# SCH_SIM.net
KiCad netlist of a schematic drawn in Altium Designer
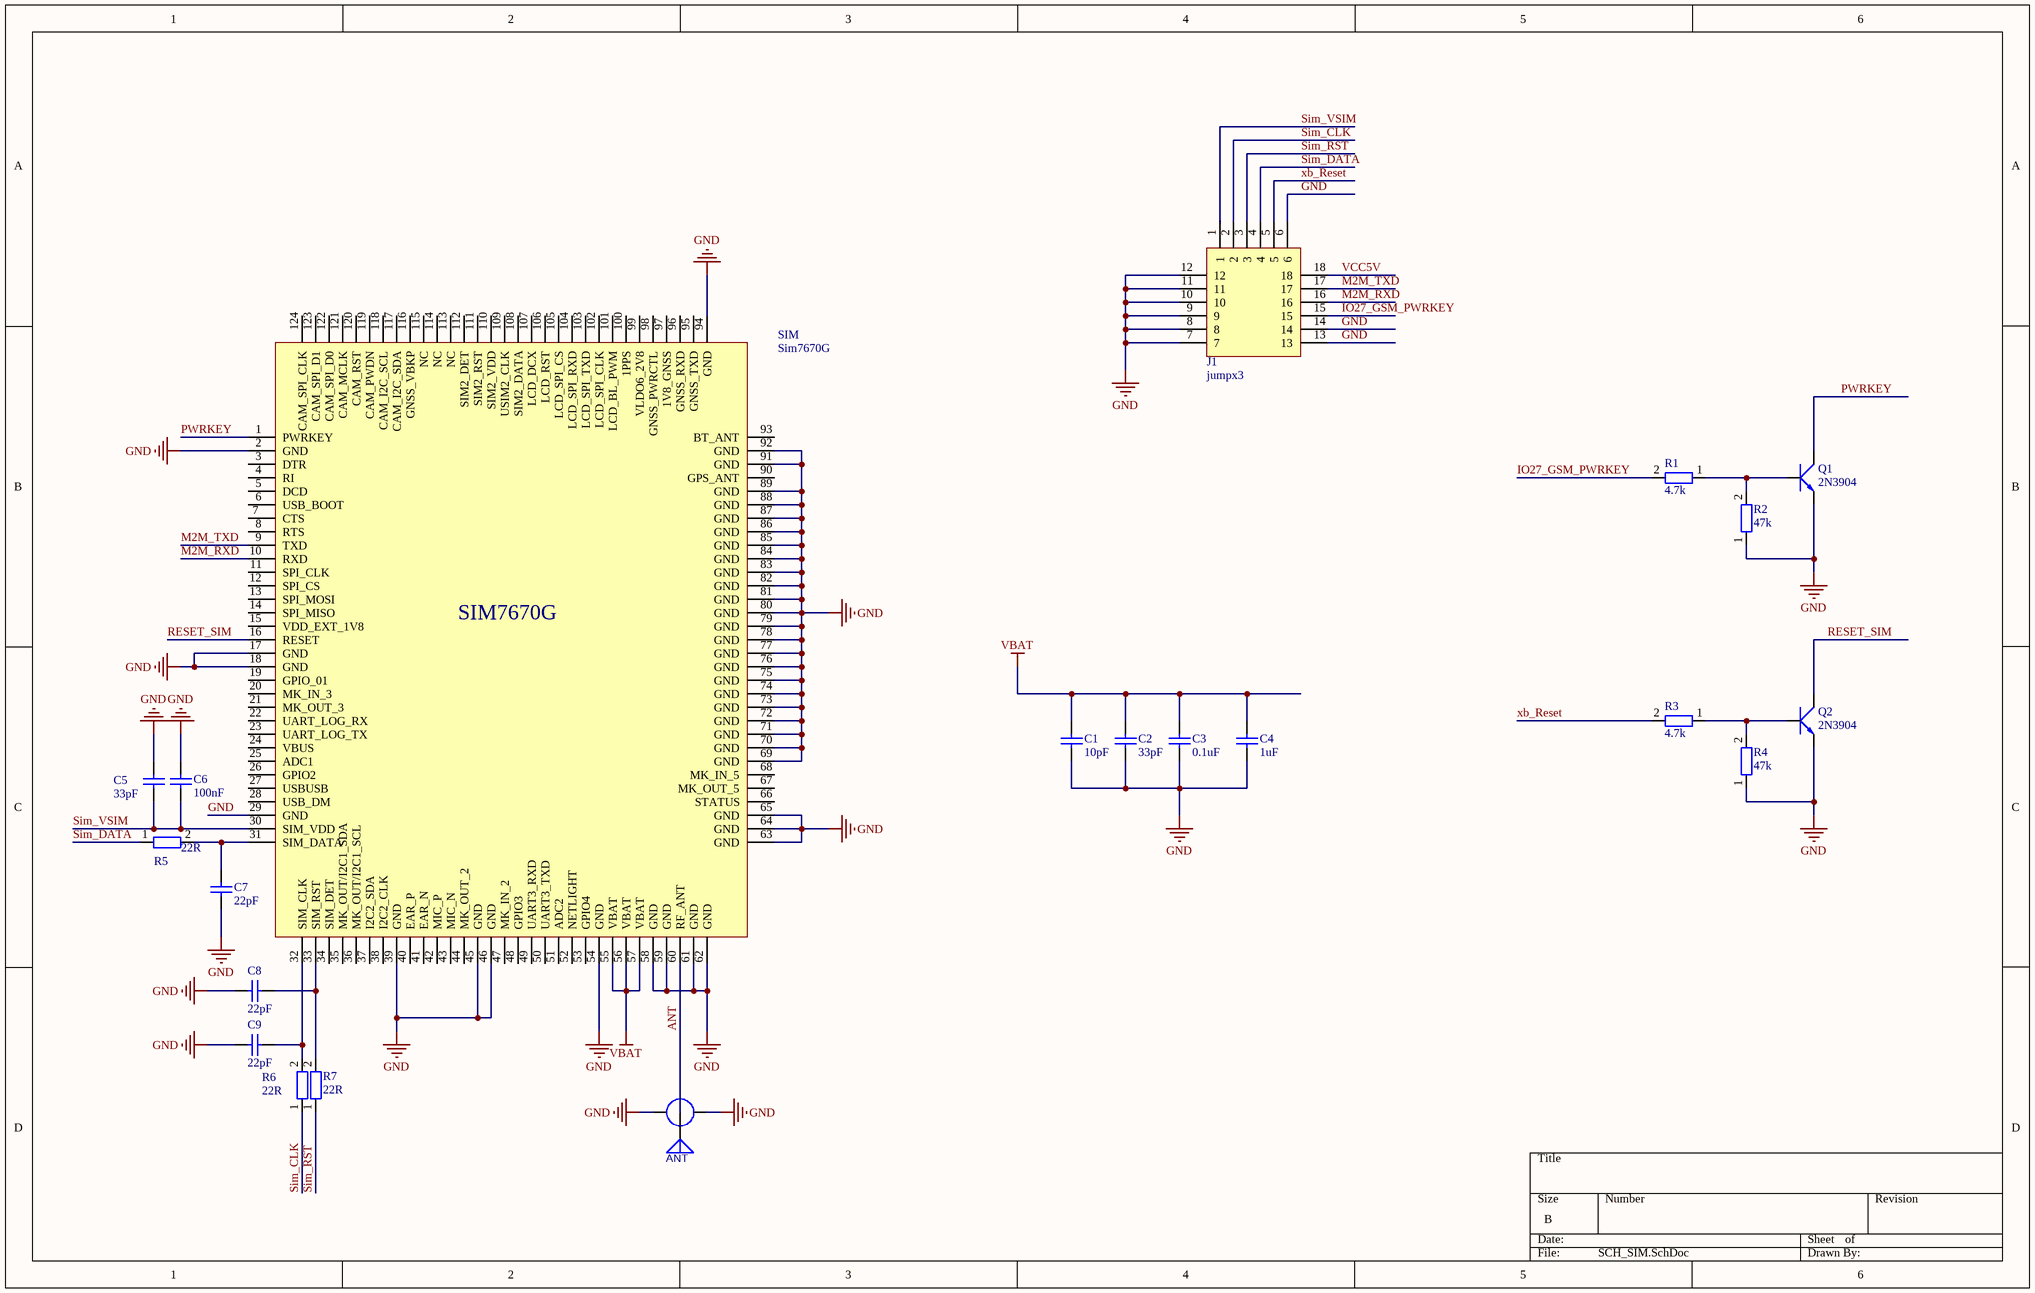
[diagram p0: SCH_SIM.SchDoc]

(export (version "E")
  (design (tool "Eeschema 10.0.6"))
  (components
    (comp (ref "ANT")
      (value "ANT")
      (footprint "CONNECTORS RF SMD TYPE IPEX")
      (description "SMD RF Connectors / Coaxial Connectors ROHS")
      (fields
        (field (name "BOM_SUPPLIER PART") "C3151745")
        (field (name "BOM_MANUFACTURER PART") "IPEX1-TXZ 142")
        (field (name "CONTRIBUTOR") "lcsc")
      )
      (libsource (lib "SCH_Library") (part "CONNECTORS RF SMD"))
    )
    (comp (ref "C1")
      (value "10pF")
      (footprint "CAP_0805")
      (description "Capacitor")
      (libsource (lib "SCH_Library") (part "CAP104-100nF-50V"))
    )
    (comp (ref "C2")
      (value "33pF")
      (footprint "CAP_0805")
      (description "Capacitor")
      (libsource (lib "SCH_Library") (part "CAP104-100nF-50V"))
    )
    (comp (ref "C3")
      (value "0.1uF")
      (footprint "CAP_0805")
      (description "Capacitor")
      (libsource (lib "SCH_Library") (part "CAP104-100nF-50V"))
    )
    (comp (ref "C4")
      (value "1uF")
      (footprint "CAP_0805")
      (description "Capacitor")
      (libsource (lib "SCH_Library") (part "CAP104-100nF-50V"))
    )
    (comp (ref "C5")
      (value "33pF")
      (footprint "CAP_0805")
      (description "Capacitor")
      (libsource (lib "SCH_Library") (part "CAP104-100nF-50V"))
    )
    (comp (ref "C6")
      (value "100nF")
      (footprint "CAP_0805")
      (description "Capacitor")
      (libsource (lib "SCH_Library") (part "CAP104-100nF-50V"))
    )
    (comp (ref "C7")
      (value "22pF")
      (footprint "CAP_0805")
      (description "Capacitor")
      (libsource (lib "SCH_Library") (part "CAP104-100nF-50V"))
    )
    (comp (ref "C8")
      (value "22pF")
      (footprint "CAP_0805")
      (description "Capacitor")
      (libsource (lib "SCH_Library") (part "CAP104-100nF-50V"))
    )
    (comp (ref "C9")
      (value "22pF")
      (footprint "CAP_0805")
      (description "Capacitor")
      (libsource (lib "SCH_Library") (part "CAP104-100nF-50V"))
    )
    (comp (ref "J1") (value "jumpx3") (libsource (lib "SCH_Library") (part "jumpx3")))
    (comp (ref "Q1")
      (value "2N3904")
      (footprint "SOT-23")
      (description "SOT-23 - C8658")
      (libsource (lib "Altium_Lib") (part "Trans BC817"))
    )
    (comp (ref "Q2")
      (value "2N3904")
      (footprint "SOT-23")
      (description "SOT-23 - C8658")
      (libsource (lib "Altium_Lib") (part "Trans BC817"))
    )
    (comp (ref "R1")
      (value "4.7k")
      (footprint "RES CHIPS SMD 0603 TYPE 1608")
      (description "±1% - Chip Resistor - Surface Mount ROHS")
      (libsource (lib "SCH_Library") (part "RES 0603 1%_"))
    )
    (comp (ref "R2")
      (value "47k")
      (footprint "RES CHIPS SMD 0603 TYPE 1608")
      (description "±1% - Chip Resistor - Surface Mount ROHS")
      (libsource (lib "SCH_Library") (part "RES 0603 1%_"))
    )
    (comp (ref "R3")
      (value "4.7k")
      (footprint "RES CHIPS SMD 0603 TYPE 1608")
      (description "±1% - Chip Resistor - Surface Mount ROHS")
      (libsource (lib "SCH_Library") (part "RES 0603 1%_"))
    )
    (comp (ref "R4")
      (value "47k")
      (footprint "RES CHIPS SMD 0603 TYPE 1608")
      (description "±1% - Chip Resistor - Surface Mount ROHS")
      (libsource (lib "SCH_Library") (part "RES 0603 1%_"))
    )
    (comp (ref "R5")
      (value "22R")
      (footprint "RES CHIPS SMD 0603 TYPE 1608")
      (description "±1% - Chip Resistor - Surface Mount ROHS")
      (libsource (lib "SCH_Library") (part "RES 0603 1%_"))
    )
    (comp (ref "R6")
      (value "22R")
      (footprint "RES CHIPS SMD 0603 TYPE 1608")
      (description "±1% - Chip Resistor - Surface Mount ROHS")
      (libsource (lib "SCH_Library") (part "RES 0603 1%_"))
    )
    (comp (ref "R7")
      (value "22R")
      (footprint "RES CHIPS SMD 0603 TYPE 1608")
      (description "±1% - Chip Resistor - Surface Mount ROHS")
      (libsource (lib "SCH_Library") (part "RES 0603 1%_"))
    )
    (comp (ref "SIM")
      (value "Sim7670G")
      (footprint "SIM7670")
      (libsource (lib "SCH_Library") (part "Sim7670G"))
    )
  )
  (nets
    (net (code "1") (name "/ANT") (class "Default")
      (node (ref "ANT") (pin "1") (pinfunction "1_1") (pintype "passive"))
      (node (ref "SIM") (pin "60") (pinfunction "RF_ANT_60") (pintype "passive"))
    )
    (net (code "2") (name "/IO27_GSM_PWRKEY") (class "Default")
      (node (ref "J1") (pin "15") (pinfunction "15_15") (pintype "passive"))
      (node (ref "R1") (pin "2") (pinfunction "2_2") (pintype "passive"))
    )
    (net (code "3") (name "/M2M_RXD") (class "Default")
      (node (ref "J1") (pin "16") (pinfunction "16_16") (pintype "passive"))
      (node (ref "SIM") (pin "10") (pinfunction "RXD_10") (pintype "passive"))
    )
    (net (code "4") (name "/M2M_TXD") (class "Default")
      (node (ref "J1") (pin "17") (pinfunction "17_17") (pintype "passive"))
      (node (ref "SIM") (pin "9") (pinfunction "TXD_9") (pintype "passive"))
    )
    (net (code "5") (name "/PWRKEY") (class "Default")
      (node (ref "Q1") (pin "3") (pinfunction "C_3") (pintype "passive"))
      (node (ref "SIM") (pin "1") (pinfunction "PWRKEY_1") (pintype "passive"))
    )
    (net (code "6") (name "/RESET_SIM") (class "Default")
      (node (ref "Q2") (pin "3") (pinfunction "C_3") (pintype "passive"))
      (node (ref "SIM") (pin "16") (pinfunction "RESET_16") (pintype "passive"))
    )
    (net (code "7") (name "/Sim_CLK") (class "Default")
      (node (ref "J1") (pin "2") (pinfunction "2_2") (pintype "passive"))
      (node (ref "R6") (pin "1") (pinfunction "1_1") (pintype "passive"))
    )
    (net (code "8") (name "/Sim_DATA") (class "Default")
      (node (ref "J1") (pin "4") (pinfunction "4_4") (pintype "passive"))
      (node (ref "R5") (pin "1") (pinfunction "1_1") (pintype "passive"))
    )
    (net (code "9") (name "/Sim_RST") (class "Default")
      (node (ref "J1") (pin "3") (pinfunction "3_3") (pintype "passive"))
      (node (ref "R7") (pin "1") (pinfunction "1_1") (pintype "passive"))
    )
    (net (code "10") (name "/Sim_VSIM") (class "Default")
      (node (ref "C5") (pin "2") (pinfunction "2_2") (pintype "passive"))
      (node (ref "C6") (pin "2") (pinfunction "2_2") (pintype "passive"))
      (node (ref "J1") (pin "1") (pinfunction "1_1") (pintype "passive"))
      (node (ref "SIM") (pin "30") (pinfunction "SIM_VDD_30") (pintype "passive"))
    )
    (net (code "11") (name "/VCC5V") (class "Default")
      (node (ref "J1") (pin "18") (pinfunction "18_18") (pintype "passive"))
    )
    (net (code "12") (name "/xb_Reset") (class "Default")
      (node (ref "J1") (pin "5") (pinfunction "5_5") (pintype "passive"))
      (node (ref "R3") (pin "2") (pinfunction "2_2") (pintype "passive"))
    )
    (net (code "13") (name "GND") (class "Default")
      (node (ref "ANT") (pin "2") (pinfunction "2_2") (pintype "passive"))
      (node (ref "ANT") (pin "3") (pinfunction "3_3") (pintype "passive"))
      (node (ref "C1") (pin "1") (pinfunction "1_1") (pintype "passive"))
      (node (ref "C2") (pin "1") (pinfunction "1_1") (pintype "passive"))
      (node (ref "C3") (pin "1") (pinfunction "1_1") (pintype "passive"))
      (node (ref "C4") (pin "1") (pinfunction "1_1") (pintype "passive"))
      (node (ref "C5") (pin "1") (pinfunction "1_1") (pintype "passive"))
      (node (ref "C6") (pin "1") (pinfunction "1_1") (pintype "passive"))
      (node (ref "C7") (pin "2") (pinfunction "2_2") (pintype "passive"))
      (node (ref "C8") (pin "2") (pinfunction "2_2") (pintype "passive"))
      (node (ref "C9") (pin "2") (pinfunction "2_2") (pintype "passive"))
      (node (ref "J1") (pin "10") (pinfunction "10_10") (pintype "passive"))
      (node (ref "J1") (pin "11") (pinfunction "11_11") (pintype "passive"))
      (node (ref "J1") (pin "12") (pinfunction "12_12") (pintype "passive"))
      (node (ref "J1") (pin "13") (pinfunction "13_13") (pintype "passive"))
      (node (ref "J1") (pin "14") (pinfunction "14_14") (pintype "passive"))
      (node (ref "J1") (pin "6") (pinfunction "6_6") (pintype "passive"))
      (node (ref "J1") (pin "7") (pinfunction "7_7") (pintype "passive"))
      (node (ref "J1") (pin "8") (pinfunction "8_8") (pintype "passive"))
      (node (ref "J1") (pin "9") (pinfunction "9_9") (pintype "passive"))
      (node (ref "Q1") (pin "2") (pinfunction "E_2") (pintype "passive"))
      (node (ref "Q2") (pin "2") (pinfunction "E_2") (pintype "passive"))
      (node (ref "R2") (pin "1") (pinfunction "1_1") (pintype "passive"))
      (node (ref "R4") (pin "1") (pinfunction "1_1") (pintype "passive"))
      (node (ref "SIM") (pin "17") (pinfunction "GND_17") (pintype "passive"))
      (node (ref "SIM") (pin "18") (pinfunction "GND_18") (pintype "passive"))
      (node (ref "SIM") (pin "2") (pinfunction "GND_2") (pintype "passive"))
      (node (ref "SIM") (pin "29") (pinfunction "GND_29") (pintype "passive"))
      (node (ref "SIM") (pin "39") (pinfunction "GND_39") (pintype "passive"))
      (node (ref "SIM") (pin "45") (pinfunction "GND_45") (pintype "passive"))
      (node (ref "SIM") (pin "46") (pinfunction "GND_46") (pintype "passive"))
      (node (ref "SIM") (pin "54") (pinfunction "GND_54") (pintype "passive"))
      (node (ref "SIM") (pin "58") (pinfunction "GND_58") (pintype "passive"))
      (node (ref "SIM") (pin "59") (pinfunction "GND_59") (pintype "passive"))
      (node (ref "SIM") (pin "61") (pinfunction "GND_61") (pintype "passive"))
      (node (ref "SIM") (pin "62") (pinfunction "GND_62") (pintype "passive"))
      (node (ref "SIM") (pin "63") (pinfunction "GND_63") (pintype "passive"))
      (node (ref "SIM") (pin "64") (pinfunction "GND_64") (pintype "passive"))
      (node (ref "SIM") (pin "65") (pinfunction "GND_65") (pintype "passive"))
      (node (ref "SIM") (pin "69") (pinfunction "GND_69") (pintype "passive"))
      (node (ref "SIM") (pin "70") (pinfunction "GND_70") (pintype "passive"))
      (node (ref "SIM") (pin "71") (pinfunction "GND_71") (pintype "passive"))
      (node (ref "SIM") (pin "72") (pinfunction "GND_72") (pintype "passive"))
      (node (ref "SIM") (pin "73") (pinfunction "GND_73") (pintype "passive"))
      (node (ref "SIM") (pin "74") (pinfunction "GND_74") (pintype "passive"))
      (node (ref "SIM") (pin "75") (pinfunction "GND_75") (pintype "passive"))
      (node (ref "SIM") (pin "76") (pinfunction "GND_76") (pintype "passive"))
      (node (ref "SIM") (pin "77") (pinfunction "GND_77") (pintype "passive"))
      (node (ref "SIM") (pin "78") (pinfunction "GND_78") (pintype "passive"))
      (node (ref "SIM") (pin "79") (pinfunction "GND_79") (pintype "passive"))
      (node (ref "SIM") (pin "80") (pinfunction "GND_80") (pintype "passive"))
      (node (ref "SIM") (pin "81") (pinfunction "GND_81") (pintype "passive"))
      (node (ref "SIM") (pin "82") (pinfunction "GND_82") (pintype "passive"))
      (node (ref "SIM") (pin "83") (pinfunction "GND_83") (pintype "passive"))
      (node (ref "SIM") (pin "84") (pinfunction "GND_84") (pintype "passive"))
      (node (ref "SIM") (pin "85") (pinfunction "GND_85") (pintype "passive"))
      (node (ref "SIM") (pin "86") (pinfunction "GND_86") (pintype "passive"))
      (node (ref "SIM") (pin "87") (pinfunction "GND_87") (pintype "passive"))
      (node (ref "SIM") (pin "88") (pinfunction "GND_88") (pintype "passive"))
      (node (ref "SIM") (pin "89") (pinfunction "GND_89") (pintype "passive"))
      (node (ref "SIM") (pin "91") (pinfunction "GND_91") (pintype "passive"))
      (node (ref "SIM") (pin "92") (pinfunction "GND_92") (pintype "passive"))
      (node (ref "SIM") (pin "94") (pinfunction "GND_94") (pintype "passive"))
    )
    (net (code "14") (name "Net-(Q1-B)") (class "Default")
      (node (ref "Q1") (pin "1") (pinfunction "B_1") (pintype "passive"))
      (node (ref "R1") (pin "1") (pinfunction "1_1") (pintype "passive"))
      (node (ref "R2") (pin "2") (pinfunction "2_2") (pintype "passive"))
    )
    (net (code "15") (name "Net-(Q2-B)") (class "Default")
      (node (ref "Q2") (pin "1") (pinfunction "B_1") (pintype "passive"))
      (node (ref "R3") (pin "1") (pinfunction "1_1") (pintype "passive"))
      (node (ref "R4") (pin "2") (pinfunction "2_2") (pintype "passive"))
    )
    (net (code "16") (name "Net-(SIM-SIM_CLK)") (class "Default")
      (node (ref "C9") (pin "1") (pinfunction "1_1") (pintype "passive"))
      (node (ref "R6") (pin "2") (pinfunction "2_2") (pintype "passive"))
      (node (ref "SIM") (pin "32") (pinfunction "SIM_CLK_32") (pintype "passive"))
    )
    (net (code "17") (name "Net-(SIM-SIM_DATA)") (class "Default")
      (node (ref "C7") (pin "1") (pinfunction "1_1") (pintype "passive"))
      (node (ref "R5") (pin "2") (pinfunction "2_2") (pintype "passive"))
      (node (ref "SIM") (pin "31") (pinfunction "SIM_DATA_31") (pintype "passive"))
    )
    (net (code "18") (name "Net-(SIM-SIM_RST)") (class "Default")
      (node (ref "C8") (pin "1") (pinfunction "1_1") (pintype "passive"))
      (node (ref "R7") (pin "2") (pinfunction "2_2") (pintype "passive"))
      (node (ref "SIM") (pin "33") (pinfunction "SIM_RST_33") (pintype "passive"))
    )
    (net (code "19") (name "VBAT") (class "Default")
      (node (ref "C1") (pin "2") (pinfunction "2_2") (pintype "passive"))
      (node (ref "C2") (pin "2") (pinfunction "2_2") (pintype "passive"))
      (node (ref "C3") (pin "2") (pinfunction "2_2") (pintype "passive"))
      (node (ref "C4") (pin "2") (pinfunction "2_2") (pintype "passive"))
      (node (ref "SIM") (pin "55") (pinfunction "VBAT_55") (pintype "passive"))
      (node (ref "SIM") (pin "56") (pinfunction "VBAT_56") (pintype "passive"))
      (node (ref "SIM") (pin "57") (pinfunction "VBAT_57") (pintype "passive"))
    )
    (net (code "20") (name "unconnected-(SIM-1PPS-Pad100)") (class "Default")
      (node (ref "SIM") (pin "100") (pinfunction "1PPS_100") (pintype "passive"))
    )
    (net (code "21") (name "unconnected-(SIM-1V8_GNSS-Pad97)") (class "Default")
      (node (ref "SIM") (pin "97") (pinfunction "1V8_GNSS_97") (pintype "passive"))
    )
    (net (code "22") (name "unconnected-(SIM-ADC1-Pad25)") (class "Default")
      (node (ref "SIM") (pin "25") (pinfunction "ADC1_25") (pintype "passive"))
    )
    (net (code "23") (name "unconnected-(SIM-ADC2-Pad51)") (class "Default")
      (node (ref "SIM") (pin "51") (pinfunction "ADC2_51") (pintype "passive"))
    )
    (net (code "24") (name "unconnected-(SIM-BT_ANT-Pad93)") (class "Default")
      (node (ref "SIM") (pin "93") (pinfunction "BT_ANT_93") (pintype "passive"))
    )
    (net (code "25") (name "unconnected-(SIM-CAM_I2C_SCL-Pad118)") (class "Default")
      (node (ref "SIM") (pin "118") (pinfunction "CAM_I2C_SCL_118") (pintype "passive"))
    )
    (net (code "26") (name "unconnected-(SIM-CAM_I2C_SDA-Pad117)") (class "Default")
      (node (ref "SIM") (pin "117") (pinfunction "CAM_I2C_SDA_117") (pintype "passive"))
    )
    (net (code "27") (name "unconnected-(SIM-CAM_MCLK-Pad121)") (class "Default")
      (node (ref "SIM") (pin "121") (pinfunction "CAM_MCLK_121") (pintype "passive"))
    )
    (net (code "28") (name "unconnected-(SIM-CAM_PWDN-Pad119)") (class "Default")
      (node (ref "SIM") (pin "119") (pinfunction "CAM_PWDN_119") (pintype "passive"))
    )
    (net (code "29") (name "unconnected-(SIM-CAM_RST-Pad120)") (class "Default")
      (node (ref "SIM") (pin "120") (pinfunction "CAM_RST_120") (pintype "passive"))
    )
    (net (code "30") (name "unconnected-(SIM-CAM_SPI_CLK-Pad124)") (class "Default")
      (node (ref "SIM") (pin "124") (pinfunction "CAM_SPI_CLK_124") (pintype "passive"))
    )
    (net (code "31") (name "unconnected-(SIM-CAM_SPI_D0-Pad122)") (class "Default")
      (node (ref "SIM") (pin "122") (pinfunction "CAM_SPI_D0_122") (pintype "passive"))
    )
    (net (code "32") (name "unconnected-(SIM-CAM_SPI_D1-Pad123)") (class "Default")
      (node (ref "SIM") (pin "123") (pinfunction "CAM_SPI_D1_123") (pintype "passive"))
    )
    (net (code "33") (name "unconnected-(SIM-CTS-Pad7)") (class "Default")
      (node (ref "SIM") (pin "7") (pinfunction "CTS_7") (pintype "passive"))
    )
    (net (code "34") (name "unconnected-(SIM-DCD-Pad5)") (class "Default")
      (node (ref "SIM") (pin "5") (pinfunction "DCD_5") (pintype "passive"))
    )
    (net (code "35") (name "unconnected-(SIM-DTR-Pad3)") (class "Default")
      (node (ref "SIM") (pin "3") (pinfunction "DTR_3") (pintype "passive"))
    )
    (net (code "36") (name "unconnected-(SIM-EAR_N-Pad41)") (class "Default")
      (node (ref "SIM") (pin "41") (pinfunction "EAR_N_41") (pintype "passive"))
    )
    (net (code "37") (name "unconnected-(SIM-EAR_P-Pad40)") (class "Default")
      (node (ref "SIM") (pin "40") (pinfunction "EAR_P_40") (pintype "passive"))
    )
    (net (code "38") (name "unconnected-(SIM-GNSS_PWRCTL-Pad98)") (class "Default")
      (node (ref "SIM") (pin "98") (pinfunction "GNSS_PWRCTL_98") (pintype "passive"))
    )
    (net (code "39") (name "unconnected-(SIM-GNSS_RXD-Pad96)") (class "Default")
      (node (ref "SIM") (pin "96") (pinfunction "GNSS_RXD_96") (pintype "passive"))
    )
    (net (code "40") (name "unconnected-(SIM-GNSS_TXD-Pad95)") (class "Default")
      (node (ref "SIM") (pin "95") (pinfunction "GNSS_TXD_95") (pintype "passive"))
    )
    (net (code "41") (name "unconnected-(SIM-GNSS_VBKP-Pad116)") (class "Default")
      (node (ref "SIM") (pin "116") (pinfunction "GNSS_VBKP_116") (pintype "passive"))
    )
    (net (code "42") (name "unconnected-(SIM-GPIO2-Pad26)") (class "Default")
      (node (ref "SIM") (pin "26") (pinfunction "GPIO2_26") (pintype "passive"))
    )
    (net (code "43") (name "unconnected-(SIM-GPIO3-Pad48)") (class "Default")
      (node (ref "SIM") (pin "48") (pinfunction "GPIO3_48") (pintype "passive"))
    )
    (net (code "44") (name "unconnected-(SIM-GPIO4-Pad53)") (class "Default")
      (node (ref "SIM") (pin "53") (pinfunction "GPIO4_53") (pintype "passive"))
    )
    (net (code "45") (name "unconnected-(SIM-GPIO_01-Pad19)") (class "Default")
      (node (ref "SIM") (pin "19") (pinfunction "GPIO_01_19") (pintype "passive"))
    )
    (net (code "46") (name "unconnected-(SIM-GPS_ANT-Pad90)") (class "Default")
      (node (ref "SIM") (pin "90") (pinfunction "GPS_ANT_90") (pintype "passive"))
    )
    (net (code "47") (name "unconnected-(SIM-I2C2_CLK-Pad38)") (class "Default")
      (node (ref "SIM") (pin "38") (pinfunction "I2C2_CLK_38") (pintype "passive"))
    )
    (net (code "48") (name "unconnected-(SIM-I2C2_SDA-Pad37)") (class "Default")
      (node (ref "SIM") (pin "37") (pinfunction "I2C2_SDA_37") (pintype "passive"))
    )
    (net (code "49") (name "unconnected-(SIM-LCD_BL_PWM-Pad101)") (class "Default")
      (node (ref "SIM") (pin "101") (pinfunction "LCD_BL_PWM_101") (pintype "passive"))
    )
    (net (code "50") (name "unconnected-(SIM-LCD_DCX-Pad107)") (class "Default")
      (node (ref "SIM") (pin "107") (pinfunction "LCD_DCX_107") (pintype "passive"))
    )
    (net (code "51") (name "unconnected-(SIM-LCD_RST-Pad106)") (class "Default")
      (node (ref "SIM") (pin "106") (pinfunction "LCD_RST_106") (pintype "passive"))
    )
    (net (code "52") (name "unconnected-(SIM-LCD_SPI_CLK-Pad102)") (class "Default")
      (node (ref "SIM") (pin "102") (pinfunction "LCD_SPI_CLK_102") (pintype "passive"))
    )
    (net (code "53") (name "unconnected-(SIM-LCD_SPI_CS-Pad105)") (class "Default")
      (node (ref "SIM") (pin "105") (pinfunction "LCD_SPI_CS_105") (pintype "passive"))
    )
    (net (code "54") (name "unconnected-(SIM-LCD_SPI_RXD-Pad104)") (class "Default")
      (node (ref "SIM") (pin "104") (pinfunction "LCD_SPI_RXD_104") (pintype "passive"))
    )
    (net (code "55") (name "unconnected-(SIM-LCD_SPI_TXD-Pad103)") (class "Default")
      (node (ref "SIM") (pin "103") (pinfunction "LCD_SPI_TXD_103") (pintype "passive"))
    )
    (net (code "56") (name "unconnected-(SIM-MIC_N-Pad43)") (class "Default")
      (node (ref "SIM") (pin "43") (pinfunction "MIC_N_43") (pintype "passive"))
    )
    (net (code "57") (name "unconnected-(SIM-MIC_P-Pad42)") (class "Default")
      (node (ref "SIM") (pin "42") (pinfunction "MIC_P_42") (pintype "passive"))
    )
    (net (code "58") (name "unconnected-(SIM-MK_IN_2-Pad47)") (class "Default")
      (node (ref "SIM") (pin "47") (pinfunction "MK_IN_2_47") (pintype "passive"))
    )
    (net (code "59") (name "unconnected-(SIM-MK_IN_3-Pad20)") (class "Default")
      (node (ref "SIM") (pin "20") (pinfunction "MK_IN_3_20") (pintype "passive"))
    )
    (net (code "60") (name "unconnected-(SIM-MK_IN_5-Pad68)") (class "Default")
      (node (ref "SIM") (pin "68") (pinfunction "MK_IN_5_68") (pintype "passive"))
    )
    (net (code "61") (name "unconnected-(SIM-MK_OUT_2-Pad44)") (class "Default")
      (node (ref "SIM") (pin "44") (pinfunction "MK_OUT_2_44") (pintype "passive"))
    )
    (net (code "62") (name "unconnected-(SIM-MK_OUT_3-Pad21)") (class "Default")
      (node (ref "SIM") (pin "21") (pinfunction "MK_OUT_3_21") (pintype "passive"))
    )
    (net (code "63") (name "unconnected-(SIM-MK_OUT_5-Pad67)") (class "Default")
      (node (ref "SIM") (pin "67") (pinfunction "MK_OUT_5_67") (pintype "passive"))
    )
    (net (code "64") (name "unconnected-(SIM-MK_OUT{slash}I2C1_SCL-Pad36)") (class "Default")
      (node (ref "SIM") (pin "36") (pinfunction "MK_OUT/I2C1_SCL_36") (pintype "passive"))
    )
    (net (code "65") (name "unconnected-(SIM-MK_OUT{slash}I2C1_SDA-Pad35)") (class "Default")
      (node (ref "SIM") (pin "35") (pinfunction "MK_OUT/I2C1_SDA_35") (pintype "passive"))
    )
    (net (code "66") (name "unconnected-(SIM-NC-Pad113)") (class "Default")
      (node (ref "SIM") (pin "113") (pinfunction "NC_113") (pintype "passive"))
    )
    (net (code "67") (name "unconnected-(SIM-NC-Pad114)") (class "Default")
      (node (ref "SIM") (pin "114") (pinfunction "NC_114") (pintype "passive"))
    )
    (net (code "68") (name "unconnected-(SIM-NC-Pad115)") (class "Default")
      (node (ref "SIM") (pin "115") (pinfunction "NC_115") (pintype "passive"))
    )
    (net (code "69") (name "unconnected-(SIM-NETLIGHT-Pad52)") (class "Default")
      (node (ref "SIM") (pin "52") (pinfunction "NETLIGHT_52") (pintype "passive"))
    )
    (net (code "70") (name "unconnected-(SIM-RI-Pad4)") (class "Default")
      (node (ref "SIM") (pin "4") (pinfunction "RI_4") (pintype "passive"))
    )
    (net (code "71") (name "unconnected-(SIM-RTS-Pad8)") (class "Default")
      (node (ref "SIM") (pin "8") (pinfunction "RTS_8") (pintype "passive"))
    )
    (net (code "72") (name "unconnected-(SIM-SIM2_DATA-Pad108)") (class "Default")
      (node (ref "SIM") (pin "108") (pinfunction "SIM2_DATA_108") (pintype "passive"))
    )
    (net (code "73") (name "unconnected-(SIM-SIM2_DET-Pad112)") (class "Default")
      (node (ref "SIM") (pin "112") (pinfunction "SIM2_DET_112") (pintype "passive"))
    )
    (net (code "74") (name "unconnected-(SIM-SIM2_RST-Pad111)") (class "Default")
      (node (ref "SIM") (pin "111") (pinfunction "SIM2_RST_111") (pintype "passive"))
    )
    (net (code "75") (name "unconnected-(SIM-SIM2_VDD-Pad110)") (class "Default")
      (node (ref "SIM") (pin "110") (pinfunction "SIM2_VDD_110") (pintype "passive"))
    )
    (net (code "76") (name "unconnected-(SIM-SIM_DET-Pad34)") (class "Default")
      (node (ref "SIM") (pin "34") (pinfunction "SIM_DET_34") (pintype "passive"))
    )
    (net (code "77") (name "unconnected-(SIM-SPI_CLK-Pad11)") (class "Default")
      (node (ref "SIM") (pin "11") (pinfunction "SPI_CLK_11") (pintype "passive"))
    )
    (net (code "78") (name "unconnected-(SIM-SPI_CS-Pad12)") (class "Default")
      (node (ref "SIM") (pin "12") (pinfunction "SPI_CS_12") (pintype "passive"))
    )
    (net (code "79") (name "unconnected-(SIM-SPI_MISO-Pad14)") (class "Default")
      (node (ref "SIM") (pin "14") (pinfunction "SPI_MISO_14") (pintype "passive"))
    )
    (net (code "80") (name "unconnected-(SIM-SPI_MOSI-Pad13)") (class "Default")
      (node (ref "SIM") (pin "13") (pinfunction "SPI_MOSI_13") (pintype "passive"))
    )
    (net (code "81") (name "unconnected-(SIM-STATUS-Pad66)") (class "Default")
      (node (ref "SIM") (pin "66") (pinfunction "STATUS_66") (pintype "passive"))
    )
    (net (code "82") (name "unconnected-(SIM-UART3_RXD-Pad49)") (class "Default")
      (node (ref "SIM") (pin "49") (pinfunction "UART3_RXD_49") (pintype "passive"))
    )
    (net (code "83") (name "unconnected-(SIM-UART3_TXD-Pad50)") (class "Default")
      (node (ref "SIM") (pin "50") (pinfunction "UART3_TXD_50") (pintype "passive"))
    )
    (net (code "84") (name "unconnected-(SIM-UART_LOG_RX-Pad22)") (class "Default")
      (node (ref "SIM") (pin "22") (pinfunction "UART_LOG_RX_22") (pintype "passive"))
    )
    (net (code "85") (name "unconnected-(SIM-UART_LOG_TX-Pad23)") (class "Default")
      (node (ref "SIM") (pin "23") (pinfunction "UART_LOG_TX_23") (pintype "passive"))
    )
    (net (code "86") (name "unconnected-(SIM-USBUSB-Pad27)") (class "Default")
      (node (ref "SIM") (pin "27") (pinfunction "USBUSB_27") (pintype "passive"))
    )
    (net (code "87") (name "unconnected-(SIM-USB_BOOT-Pad6)") (class "Default")
      (node (ref "SIM") (pin "6") (pinfunction "USB_BOOT_6") (pintype "passive"))
    )
    (net (code "88") (name "unconnected-(SIM-USB_DM-Pad28)") (class "Default")
      (node (ref "SIM") (pin "28") (pinfunction "USB_DM_28") (pintype "passive"))
    )
    (net (code "89") (name "unconnected-(SIM-USIM2_CLK-Pad109)") (class "Default")
      (node (ref "SIM") (pin "109") (pinfunction "USIM2_CLK_109") (pintype "passive"))
    )
    (net (code "90") (name "unconnected-(SIM-VBUS-Pad24)") (class "Default")
      (node (ref "SIM") (pin "24") (pinfunction "VBUS_24") (pintype "passive"))
    )
    (net (code "91") (name "unconnected-(SIM-VDD_EXT_1V8-Pad15)") (class "Default")
      (node (ref "SIM") (pin "15") (pinfunction "VDD_EXT_1V8_15") (pintype "passive"))
    )
    (net (code "92") (name "unconnected-(SIM-VLDO6_2V8-Pad99)") (class "Default")
      (node (ref "SIM") (pin "99") (pinfunction "VLDO6_2V8_99") (pintype "passive"))
    )
  )
)
